# OpIoT_v_1_2.net
KiCad netlist of a schematic drawn in EAGLE
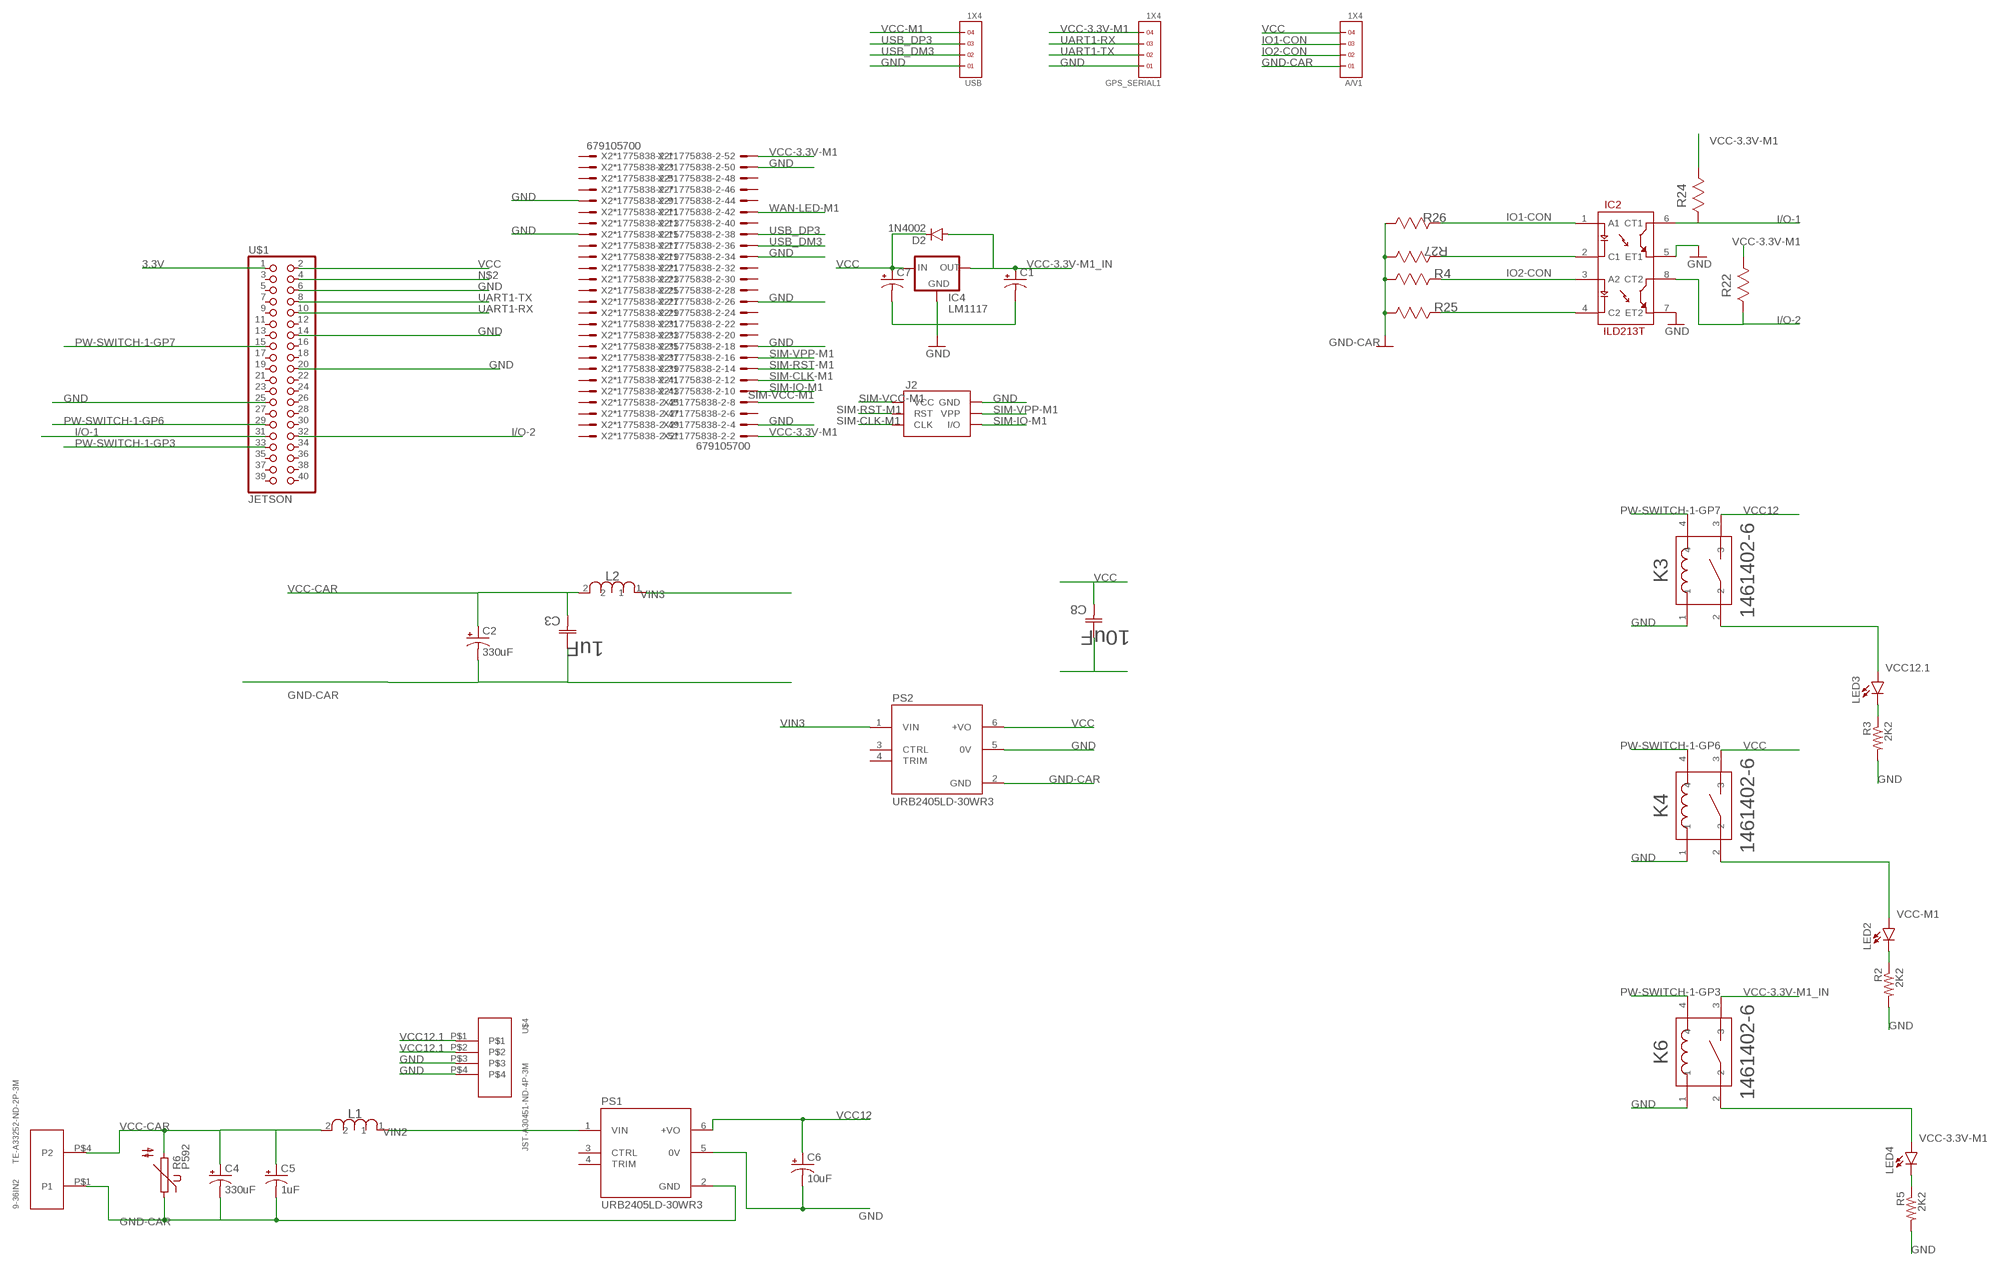
[diagram p0: schematic, sheet 1]

(export (version "E")
  (design (tool "Eeschema 10.0.6"))
  (components
    (comp (ref "9-36IN2")
      (value "TE-A33252-ND-2P-3M")
      (footprint "eagle-import:TE-A33252-ND-2P-3M")
      (libsource (lib "eagle-import") (part "TE-A33252-ND-2P-3M"))
    )
    (comp (ref "A/V1")
      (value "1X4")
      (footprint "eagle-import:1X4")
      (libsource (lib "eagle-import") (part "1X4"))
    )
    (comp (ref "C1")
      (value "CAP_POL1206-KIT")
      (footprint "eagle-import:EIA3216-KIT")
      (libsource (lib "eagle-import") (part "CAP_POL1206-KIT"))
    )
    (comp (ref "C2")
      (value "330uF")
      (footprint "eagle-import:UD-10X10_NICHICON")
      (libsource (lib "eagle-import") (part "CPOL-USUD-10X10"))
    )
    (comp (ref "C3")
      (value "1uF")
      (footprint "eagle-import:CAPC3216X110N")
      (fields (field (name "MPN") "C1206C105K5RACTU") (field (name "TOLERANCE") "±10%"))
      (libsource (lib "eagle-import") (part "C1206C105K5RACTU"))
    )
    (comp (ref "C4")
      (value "330uF")
      (footprint "eagle-import:UD-10X10_NICHICON")
      (libsource (lib "eagle-import") (part "CPOL-USUD-10X10"))
    )
    (comp (ref "C5")
      (value "1uF")
      (footprint "eagle-import:EIA3216-KIT")
      (libsource (lib "eagle-import") (part "CAP_POL1206-KIT"))
    )
    (comp (ref "C6")
      (value "10uF")
      (footprint "eagle-import:EIA3216-KIT")
      (libsource (lib "eagle-import") (part "CAP_POL1206-KIT"))
    )
    (comp (ref "C7")
      (value "CAP_POL1206-KIT")
      (footprint "eagle-import:EIA3216-KIT")
      (libsource (lib "eagle-import") (part "CAP_POL1206-KIT"))
    )
    (comp (ref "C8")
      (value "10uF")
      (footprint "eagle-import:CAPC3216X110N")
      (fields (field (name "MPN") "C1206C105K5RACTU") (field (name "TOLERANCE") "±10%"))
      (libsource (lib "eagle-import") (part "C1206C105K5RACTU"))
    )
    (comp (ref "D2")
      (value "1N4002")
      (footprint "eagle-import:SMA-DIODE-KIT")
      (libsource (lib "eagle-import") (part "DIODESMA-KIT"))
    )
    (comp (ref "GPS_SERIAL1")
      (value "1X4")
      (footprint "eagle-import:1X4")
      (libsource (lib "eagle-import") (part "1X4"))
    )
    (comp (ref "IC2")
      (value "ILD213T")
      (footprint "eagle-import:SO08")
      (libsource (lib "eagle-import") (part "ILD213T"))
    )
    (comp (ref "IC4")
      (value "LM1117")
      (footprint "eagle-import:SOT223")
      (fields (field (name "MF") "Texas Instruments") (field (name "MP") "LM1117MP-3.3/NOPB"))
      (libsource (lib "eagle-import") (part "LM1117"))
    )
    (comp (ref "J2")
      (value "SIMHOLDERSIM")
      (footprint "eagle-import:SIMHOLDER")
      (libsource (lib "eagle-import") (part "SIMHOLDERSIM"))
    )
    (comp (ref "K3")
      (value "1461402-6")
      (footprint "eagle-import:RELAY_1461402-6")
      (fields (field (name "MF") "TE Connectivity") (field (name "MP") "OJE-SH-112HM,000"))
      (libsource (lib "eagle-import") (part "1461402-6"))
    )
    (comp (ref "K4")
      (value "1461402-6")
      (footprint "eagle-import:RELAY_1461402-6")
      (fields (field (name "MF") "TE Connectivity") (field (name "MP") "OJE-SH-112HM,000"))
      (libsource (lib "eagle-import") (part "1461402-6"))
    )
    (comp (ref "K6")
      (value "1461402-6")
      (footprint "eagle-import:RELAY_1461402-6")
      (fields (field (name "MF") "TE Connectivity") (field (name "MP") "OJE-SH-112HM,000"))
      (libsource (lib "eagle-import") (part "1461402-6"))
    )
    (comp (ref "L1")
      (value "4.7uH")
      (footprint "eagle-import:INDC3225X22N")
      (fields (field (name "MPN") "PM1210-1R0J-RC") (field (name "TOLERANCE") "±5 %"))
      (libsource (lib "eagle-import") (part "PM1210-1R0J-RC"))
    )
    (comp (ref "L2")
      (value "4.7uH")
      (footprint "eagle-import:INDC3225X22N")
      (fields (field (name "MPN") "PM1210-1R0J-RC") (field (name "TOLERANCE") "±5 %"))
      (libsource (lib "eagle-import") (part "PM1210-1R0J-RC"))
    )
    (comp (ref "LED2")
      (value "LEDCHIPLED_1206")
      (footprint "eagle-import:CHIPLED_1206")
      (libsource (lib "eagle-import") (part "LEDCHIPLED_1206"))
    )
    (comp (ref "LED3")
      (value "LEDCHIPLED_1206")
      (footprint "eagle-import:CHIPLED_1206")
      (libsource (lib "eagle-import") (part "LEDCHIPLED_1206"))
    )
    (comp (ref "LED4")
      (value "LEDCHIPLED_1206")
      (footprint "eagle-import:CHIPLED_1206")
      (libsource (lib "eagle-import") (part "LEDCHIPLED_1206"))
    )
    (comp (ref "PS1")
      (value "URB2405LD-30WR3")
      (footprint "eagle-import:CONV_URB2405LD-30WR3")
      (fields (field (name "MF") "MORNSUN"))
      (libsource (lib "eagle-import") (part "URB2405LD-30WR3"))
    )
    (comp (ref "PS2")
      (value "URB2405LD-30WR3")
      (footprint "eagle-import:CONV_URB2405LD-30WR3")
      (fields (field (name "MF") "MORNSUN"))
      (libsource (lib "eagle-import") (part "URB2405LD-30WR3"))
    )
    (comp (ref "R2")
      (value "2K2")
      (footprint "eagle-import:M1206")
      (libsource (lib "eagle-import") (part "R-US_M1206"))
    )
    (comp (ref "R3")
      (value "2K2")
      (footprint "eagle-import:M1206")
      (libsource (lib "eagle-import") (part "R-US_M1206"))
    )
    (comp (ref "R4")
      (value "4K7")
      (footprint "eagle-import:RESC3216X71N")
      (fields (field (name "MPN") "ERJ-8ENF1501V") (field (name "TOLERANCE") "±1 %"))
      (libsource (lib "eagle-import") (part "ERJ-8ENF1501V"))
    )
    (comp (ref "R5")
      (value "2K2")
      (footprint "eagle-import:M1206")
      (libsource (lib "eagle-import") (part "R-US_M1206"))
    )
    (comp (ref "R6")
      (value "P592")
      (footprint "eagle-import:P592")
      (libsource (lib "eagle-import") (part "P592"))
    )
    (comp (ref "R22")
      (value "300K")
      (footprint "eagle-import:RESC3216X71N")
      (fields (field (name "MPN") "ERJ-8ENF1501V") (field (name "TOLERANCE") "±1 %"))
      (libsource (lib "eagle-import") (part "ERJ-8ENF1501V"))
    )
    (comp (ref "R24")
      (value "300K")
      (footprint "eagle-import:RESC3216X71N")
      (fields (field (name "MPN") "ERJ-8ENF1501V") (field (name "TOLERANCE") "±1 %"))
      (libsource (lib "eagle-import") (part "ERJ-8ENF1501V"))
    )
    (comp (ref "R25")
      (value "2.2K")
      (footprint "eagle-import:RESC3216X71N")
      (fields (field (name "MPN") "ERJ-8ENF1501V") (field (name "TOLERANCE") "±1 %"))
      (libsource (lib "eagle-import") (part "ERJ-8ENF1501V"))
    )
    (comp (ref "R26")
      (value "4K7")
      (footprint "eagle-import:RESC3216X71N")
      (fields (field (name "MPN") "ERJ-8ENF1501V") (field (name "TOLERANCE") "±1 %"))
      (libsource (lib "eagle-import") (part "ERJ-8ENF1501V"))
    )
    (comp (ref "R27")
      (value "2.2K")
      (footprint "eagle-import:RESC3216X71N")
      (fields (field (name "MPN") "ERJ-8ENF1501V") (field (name "TOLERANCE") "±1 %"))
      (libsource (lib "eagle-import") (part "ERJ-8ENF1501V"))
    )
    (comp (ref "U$1")
      (value "JETSON")
      (footprint "eagle-import:2X20")
      (libsource (lib "eagle-import") (part "JETSON"))
    )
    (comp (ref "U$4")
      (value "JST-A30451-ND-4P-3M")
      (footprint "eagle-import:TE-A30451-4P-TH-3M")
      (libsource (lib "eagle-import") (part "JST-A30451-ND-4P-3M"))
    )
    (comp (ref "USB")
      (value "1X4")
      (footprint "eagle-import:1X4")
      (libsource (lib "eagle-import") (part "1X4"))
    )
    (comp (ref "X2*1775838-2")
      (value "679105700")
      (footprint "eagle-import:679105700")
      (fields (field (name "MF") "MOLEX") (field (name "MPN") "67910-5700"))
      (libsource (lib "eagle-import") (part "679105700"))
    )
  )
  (nets
    (net (code "1") (name "/3.3V") (class "Default")
      (node (ref "U$1") (pin "1") (pinfunction "1_1") (pintype "passive"))
    )
    (net (code "2") (name "/IO1-CON") (class "Default")
      (node (ref "A/V1") (pin "3") (pinfunction "3_3") (pintype "bidirectional"))
      (node (ref "IC2") (pin "1") (pinfunction "A1_1") (pintype "bidirectional"))
      (node (ref "R26") (pin "1") (pinfunction "R1_1") (pintype "passive"))
    )
    (net (code "3") (name "/IO2-CON") (class "Default")
      (node (ref "A/V1") (pin "2") (pinfunction "2_2") (pintype "bidirectional"))
      (node (ref "IC2") (pin "3") (pinfunction "A2_3") (pintype "bidirectional"))
      (node (ref "R4") (pin "1") (pinfunction "R1_1") (pintype "passive"))
    )
    (net (code "4") (name "/I{slash}O-1") (class "Default")
      (node (ref "IC2") (pin "6") (pinfunction "CT1_6") (pintype "bidirectional"))
      (node (ref "R24") (pin "2") (pinfunction "R2_2") (pintype "passive"))
      (node (ref "U$1") (pin "31") (pinfunction "31_31") (pintype "passive"))
    )
    (net (code "5") (name "/I{slash}O-2") (class "Default")
      (node (ref "IC2") (pin "8") (pinfunction "CT2_8") (pintype "bidirectional"))
      (node (ref "R22") (pin "2") (pinfunction "R2_2") (pintype "passive"))
      (node (ref "U$1") (pin "32") (pinfunction "32_32") (pintype "passive"))
    )
    (net (code "6") (name "/N$2") (class "Default")
      (node (ref "U$1") (pin "4") (pinfunction "4_4") (pintype "passive"))
    )
    (net (code "7") (name "/PW-SWITCH-1-GP3") (class "Default")
      (node (ref "K6") (pin "4") (pinfunction "4_4") (pintype "passive"))
      (node (ref "U$1") (pin "33") (pinfunction "33_33") (pintype "passive"))
    )
    (net (code "8") (name "/PW-SWITCH-1-GP6") (class "Default")
      (node (ref "K4") (pin "4") (pinfunction "4_4") (pintype "passive"))
      (node (ref "U$1") (pin "29") (pinfunction "29_29") (pintype "passive"))
    )
    (net (code "9") (name "/PW-SWITCH-1-GP7") (class "Default")
      (node (ref "K3") (pin "4") (pinfunction "4_4") (pintype "passive"))
      (node (ref "U$1") (pin "15") (pinfunction "15_15") (pintype "passive"))
    )
    (net (code "10") (name "/SIM-CLK-M1") (class "Default")
      (node (ref "J2") (pin "C3") (pinfunction "CLK_C3") (pintype "input"))
      (node (ref "X2*1775838-2") (pin "12") (pinfunction "S_12") (pintype "passive"))
    )
    (net (code "11") (name "/SIM-IO-M1") (class "Default")
      (node (ref "J2") (pin "C7") (pinfunction "I/O_C7") (pintype "bidirectional"))
      (node (ref "X2*1775838-2") (pin "10") (pinfunction "S_10") (pintype "passive"))
    )
    (net (code "12") (name "/SIM-RST-M1") (class "Default")
      (node (ref "J2") (pin "C2") (pinfunction "RST_C2") (pintype "input"))
      (node (ref "X2*1775838-2") (pin "14") (pinfunction "S_14") (pintype "passive"))
    )
    (net (code "13") (name "/SIM-VCC-M1") (class "Default")
      (node (ref "J2") (pin "C1") (pinfunction "VCC_C1") (pintype "power_in"))
      (node (ref "X2*1775838-2") (pin "8") (pinfunction "S_8") (pintype "passive"))
    )
    (net (code "14") (name "/SIM-VPP-M1") (class "Default")
      (node (ref "J2") (pin "C6") (pinfunction "VPP_C6") (pintype "input"))
      (node (ref "X2*1775838-2") (pin "16") (pinfunction "S_16") (pintype "passive"))
    )
    (net (code "15") (name "/UART1-RX") (class "Default")
      (node (ref "GPS_SERIAL1") (pin "3") (pinfunction "3_3") (pintype "bidirectional"))
      (node (ref "U$1") (pin "10") (pinfunction "10_10") (pintype "passive"))
    )
    (net (code "16") (name "/UART1-TX") (class "Default")
      (node (ref "GPS_SERIAL1") (pin "2") (pinfunction "2_2") (pintype "bidirectional"))
      (node (ref "U$1") (pin "8") (pinfunction "8_8") (pintype "passive"))
    )
    (net (code "17") (name "/USB_DM3") (class "Default")
      (node (ref "USB") (pin "2") (pinfunction "2_2") (pintype "bidirectional"))
      (node (ref "X2*1775838-2") (pin "36") (pinfunction "S_36") (pintype "passive"))
    )
    (net (code "18") (name "/USB_DP3") (class "Default")
      (node (ref "USB") (pin "3") (pinfunction "3_3") (pintype "bidirectional"))
      (node (ref "X2*1775838-2") (pin "38") (pinfunction "S_38") (pintype "passive"))
    )
    (net (code "19") (name "/VCC") (class "Default")
      (node (ref "A/V1") (pin "4") (pinfunction "4_4") (pintype "bidirectional"))
      (node (ref "C7") (pin "A") (pinfunction "+_A") (pintype "passive"))
      (node (ref "C8") (pin "2") (pinfunction "C2_2") (pintype "passive"))
      (node (ref "D2") (pin "C") (pinfunction "C_C") (pintype "passive"))
      (node (ref "IC4") (pin "3") (pinfunction "IN_3") (pintype "input"))
      (node (ref "K4") (pin "3") (pinfunction "3_3") (pintype "passive"))
      (node (ref "PS2") (pin "6") (pinfunction "+VO_6") (pintype "output"))
      (node (ref "U$1") (pin "2") (pinfunction "2_2") (pintype "passive"))
    )
    (net (code "20") (name "/VCC-3.3V-M1") (class "Default")
      (node (ref "GPS_SERIAL1") (pin "4") (pinfunction "4_4") (pintype "bidirectional"))
      (node (ref "K6") (pin "2") (pinfunction "2_2") (pintype "passive"))
      (node (ref "LED4") (pin "A") (pinfunction "A_A") (pintype "passive"))
      (node (ref "R22") (pin "1") (pinfunction "R1_1") (pintype "passive"))
      (node (ref "R24") (pin "1") (pinfunction "R1_1") (pintype "passive"))
      (node (ref "X2*1775838-2") (pin "2") (pinfunction "S_2") (pintype "passive"))
      (node (ref "X2*1775838-2") (pin "52") (pinfunction "S_52") (pintype "passive"))
    )
    (net (code "21") (name "/VCC-3.3V-M1_IN") (class "Default")
      (node (ref "C1") (pin "A") (pinfunction "+_A") (pintype "passive"))
      (node (ref "D2") (pin "A") (pinfunction "A_A") (pintype "passive"))
      (node (ref "IC4") (pin "2") (pinfunction "OUT_2") (pintype "passive"))
      (node (ref "K6") (pin "3") (pinfunction "3_3") (pintype "passive"))
    )
    (net (code "22") (name "/VCC-CAR") (class "Default")
      (node (ref "9-36IN2") (pin "P$4") (pinfunction "P2_P$4") (pintype "bidirectional"))
      (node (ref "C2") (pin "+") (pinfunction "+_+") (pintype "passive"))
      (node (ref "C3") (pin "2") (pinfunction "C2_2") (pintype "passive"))
      (node (ref "C4") (pin "+") (pinfunction "+_+") (pintype "passive"))
      (node (ref "C5") (pin "A") (pinfunction "+_A") (pintype "passive"))
      (node (ref "L1") (pin "2") (pinfunction "2_2") (pintype "passive"))
      (node (ref "L2") (pin "2") (pinfunction "2_2") (pintype "passive"))
      (node (ref "R6") (pin "2") (pinfunction "2_2") (pintype "passive"))
    )
    (net (code "23") (name "/VCC-M1") (class "Default")
      (node (ref "K4") (pin "2") (pinfunction "2_2") (pintype "passive"))
      (node (ref "LED2") (pin "A") (pinfunction "A_A") (pintype "passive"))
      (node (ref "USB") (pin "4") (pinfunction "4_4") (pintype "bidirectional"))
    )
    (net (code "24") (name "/VCC12") (class "Default")
      (node (ref "C6") (pin "A") (pinfunction "+_A") (pintype "passive"))
      (node (ref "K3") (pin "3") (pinfunction "3_3") (pintype "passive"))
      (node (ref "PS1") (pin "6") (pinfunction "+VO_6") (pintype "output"))
    )
    (net (code "25") (name "/VCC12.1") (class "Default")
      (node (ref "K3") (pin "2") (pinfunction "2_2") (pintype "passive"))
      (node (ref "LED3") (pin "A") (pinfunction "A_A") (pintype "passive"))
      (node (ref "U$4") (pin "P$1") (pinfunction "P$1_P$1") (pintype "bidirectional"))
      (node (ref "U$4") (pin "P$2") (pinfunction "P$2_P$2") (pintype "bidirectional"))
    )
    (net (code "26") (name "/VIN2") (class "Default")
      (node (ref "L1") (pin "1") (pinfunction "1_1") (pintype "passive"))
      (node (ref "PS1") (pin "1") (pinfunction "VIN_1") (pintype "input"))
    )
    (net (code "27") (name "/VIN3") (class "Default")
      (node (ref "L2") (pin "1") (pinfunction "1_1") (pintype "passive"))
      (node (ref "PS2") (pin "1") (pinfunction "VIN_1") (pintype "input"))
    )
    (net (code "28") (name "/WAN-LED-M1") (class "Default")
      (node (ref "X2*1775838-2") (pin "42") (pinfunction "S_42") (pintype "passive"))
    )
    (net (code "29") (name "GND") (class "Default")
      (node (ref "C1") (pin "C") (pinfunction "-_C") (pintype "passive"))
      (node (ref "C6") (pin "C") (pinfunction "-_C") (pintype "passive"))
      (node (ref "C7") (pin "C") (pinfunction "-_C") (pintype "passive"))
      (node (ref "C8") (pin "1") (pinfunction "C1_1") (pintype "passive"))
      (node (ref "GPS_SERIAL1") (pin "1") (pinfunction "1_1") (pintype "bidirectional"))
      (node (ref "IC2") (pin "5") (pinfunction "ET1_5") (pintype "bidirectional"))
      (node (ref "IC2") (pin "7") (pinfunction "ET2_7") (pintype "bidirectional"))
      (node (ref "IC4") (pin "1") (pinfunction "GND_1") (pintype "input"))
      (node (ref "J2") (pin "C5") (pinfunction "GND_C5") (pintype "power_in"))
      (node (ref "K3") (pin "1") (pinfunction "1_1") (pintype "passive"))
      (node (ref "K4") (pin "1") (pinfunction "1_1") (pintype "passive"))
      (node (ref "K6") (pin "1") (pinfunction "1_1") (pintype "passive"))
      (node (ref "PS1") (pin "5") (pinfunction "0V_5") (pintype "output"))
      (node (ref "PS2") (pin "5") (pinfunction "0V_5") (pintype "output"))
      (node (ref "R2") (pin "2") (pinfunction "2_2") (pintype "passive"))
      (node (ref "R3") (pin "2") (pinfunction "2_2") (pintype "passive"))
      (node (ref "R5") (pin "2") (pinfunction "2_2") (pintype "passive"))
      (node (ref "U$1") (pin "14") (pinfunction "14_14") (pintype "passive"))
      (node (ref "U$1") (pin "20") (pinfunction "20_20") (pintype "passive"))
      (node (ref "U$1") (pin "25") (pinfunction "25_25") (pintype "passive"))
      (node (ref "U$1") (pin "6") (pinfunction "6_6") (pintype "passive"))
      (node (ref "U$4") (pin "P$3") (pinfunction "P$3_P$3") (pintype "bidirectional"))
      (node (ref "U$4") (pin "P$4") (pinfunction "P$4_P$4") (pintype "bidirectional"))
      (node (ref "USB") (pin "1") (pinfunction "1_1") (pintype "bidirectional"))
      (node (ref "X2*1775838-2") (pin "15") (pinfunction "S_15") (pintype "passive"))
      (node (ref "X2*1775838-2") (pin "18") (pinfunction "S_18") (pintype "passive"))
      (node (ref "X2*1775838-2") (pin "26") (pinfunction "S_26") (pintype "passive"))
      (node (ref "X2*1775838-2") (pin "34") (pinfunction "S_34") (pintype "passive"))
      (node (ref "X2*1775838-2") (pin "4") (pinfunction "S_4") (pintype "passive"))
      (node (ref "X2*1775838-2") (pin "50") (pinfunction "S_50") (pintype "passive"))
      (node (ref "X2*1775838-2") (pin "9") (pinfunction "S_9") (pintype "passive"))
    )
    (net (code "30") (name "GND-CAR") (class "Default")
      (node (ref "9-36IN2") (pin "P$1") (pinfunction "P1_P$1") (pintype "bidirectional"))
      (node (ref "A/V1") (pin "1") (pinfunction "1_1") (pintype "bidirectional"))
      (node (ref "C2") (pin "-") (pinfunction "-_-") (pintype "passive"))
      (node (ref "C3") (pin "1") (pinfunction "C1_1") (pintype "passive"))
      (node (ref "C4") (pin "-") (pinfunction "-_-") (pintype "passive"))
      (node (ref "C5") (pin "C") (pinfunction "-_C") (pintype "passive"))
      (node (ref "PS1") (pin "2") (pinfunction "GND_2") (pintype "power_in"))
      (node (ref "PS2") (pin "2") (pinfunction "GND_2") (pintype "power_in"))
      (node (ref "R25") (pin "1") (pinfunction "R1_1") (pintype "passive"))
      (node (ref "R26") (pin "2") (pinfunction "R2_2") (pintype "passive"))
      (node (ref "R27") (pin "1") (pinfunction "R1_1") (pintype "passive"))
      (node (ref "R4") (pin "2") (pinfunction "R2_2") (pintype "passive"))
      (node (ref "R6") (pin "1") (pinfunction "1_1") (pintype "passive"))
    )
    (net (code "31") (name "Net-(IC2-C1)") (class "Default")
      (node (ref "IC2") (pin "2") (pinfunction "C1_2") (pintype "bidirectional"))
      (node (ref "R27") (pin "2") (pinfunction "R2_2") (pintype "passive"))
    )
    (net (code "32") (name "Net-(IC2-C2)") (class "Default")
      (node (ref "IC2") (pin "4") (pinfunction "C2_4") (pintype "bidirectional"))
      (node (ref "R25") (pin "2") (pinfunction "R2_2") (pintype "passive"))
    )
    (net (code "33") (name "Net-(LED2-PadC)") (class "Default")
      (node (ref "LED2") (pin "C") (pinfunction "C_C") (pintype "passive"))
      (node (ref "R2") (pin "1") (pinfunction "1_1") (pintype "passive"))
    )
    (net (code "34") (name "Net-(LED3-PadC)") (class "Default")
      (node (ref "LED3") (pin "C") (pinfunction "C_C") (pintype "passive"))
      (node (ref "R3") (pin "1") (pinfunction "1_1") (pintype "passive"))
    )
    (net (code "35") (name "Net-(LED4-PadC)") (class "Default")
      (node (ref "LED4") (pin "C") (pinfunction "C_C") (pintype "passive"))
      (node (ref "R5") (pin "1") (pinfunction "1_1") (pintype "passive"))
    )
    (net (code "36") (name "unconnected-(PS1-CTRL-Pad3)") (class "Default")
      (node (ref "PS1") (pin "3") (pinfunction "CTRL_3") (pintype "input"))
    )
    (net (code "37") (name "unconnected-(PS1-TRIM-Pad4)") (class "Default")
      (node (ref "PS1") (pin "4") (pinfunction "TRIM_4") (pintype "input"))
    )
    (net (code "38") (name "unconnected-(PS2-CTRL-Pad3)") (class "Default")
      (node (ref "PS2") (pin "3") (pinfunction "CTRL_3") (pintype "input"))
    )
    (net (code "39") (name "unconnected-(PS2-TRIM-Pad4)") (class "Default")
      (node (ref "PS2") (pin "4") (pinfunction "TRIM_4") (pintype "input"))
    )
    (net (code "40") (name "unconnected-(U$1-Pad3)") (class "Default")
      (node (ref "U$1") (pin "3") (pinfunction "3_3") (pintype "passive"))
    )
    (net (code "41") (name "unconnected-(U$1-Pad5)") (class "Default")
      (node (ref "U$1") (pin "5") (pinfunction "5_5") (pintype "passive"))
    )
    (net (code "42") (name "unconnected-(U$1-Pad7)") (class "Default")
      (node (ref "U$1") (pin "7") (pinfunction "7_7") (pintype "passive"))
    )
    (net (code "43") (name "unconnected-(U$1-Pad9)") (class "Default")
      (node (ref "U$1") (pin "9") (pinfunction "9_9") (pintype "passive"))
    )
    (net (code "44") (name "unconnected-(U$1-Pad11)") (class "Default")
      (node (ref "U$1") (pin "11") (pinfunction "11_11") (pintype "passive"))
    )
    (net (code "45") (name "unconnected-(U$1-Pad12)") (class "Default")
      (node (ref "U$1") (pin "12") (pinfunction "12_12") (pintype "passive"))
    )
    (net (code "46") (name "unconnected-(U$1-Pad13)") (class "Default")
      (node (ref "U$1") (pin "13") (pinfunction "13_13") (pintype "passive"))
    )
    (net (code "47") (name "unconnected-(U$1-Pad16)") (class "Default")
      (node (ref "U$1") (pin "16") (pinfunction "16_16") (pintype "passive"))
    )
    (net (code "48") (name "unconnected-(U$1-Pad17)") (class "Default")
      (node (ref "U$1") (pin "17") (pinfunction "17_17") (pintype "passive"))
    )
    (net (code "49") (name "unconnected-(U$1-Pad18)") (class "Default")
      (node (ref "U$1") (pin "18") (pinfunction "18_18") (pintype "passive"))
    )
    (net (code "50") (name "unconnected-(U$1-Pad19)") (class "Default")
      (node (ref "U$1") (pin "19") (pinfunction "19_19") (pintype "passive"))
    )
    (net (code "51") (name "unconnected-(U$1-Pad21)") (class "Default")
      (node (ref "U$1") (pin "21") (pinfunction "21_21") (pintype "passive"))
    )
    (net (code "52") (name "unconnected-(U$1-Pad22)") (class "Default")
      (node (ref "U$1") (pin "22") (pinfunction "22_22") (pintype "passive"))
    )
    (net (code "53") (name "unconnected-(U$1-Pad23)") (class "Default")
      (node (ref "U$1") (pin "23") (pinfunction "23_23") (pintype "passive"))
    )
    (net (code "54") (name "unconnected-(U$1-Pad24)") (class "Default")
      (node (ref "U$1") (pin "24") (pinfunction "24_24") (pintype "passive"))
    )
    (net (code "55") (name "unconnected-(U$1-Pad26)") (class "Default")
      (node (ref "U$1") (pin "26") (pinfunction "26_26") (pintype "passive"))
    )
    (net (code "56") (name "unconnected-(U$1-Pad27)") (class "Default")
      (node (ref "U$1") (pin "27") (pinfunction "27_27") (pintype "passive"))
    )
    (net (code "57") (name "unconnected-(U$1-Pad28)") (class "Default")
      (node (ref "U$1") (pin "28") (pinfunction "28_28") (pintype "passive"))
    )
    (net (code "58") (name "unconnected-(U$1-Pad30)") (class "Default")
      (node (ref "U$1") (pin "30") (pinfunction "30_30") (pintype "passive"))
    )
    (net (code "59") (name "unconnected-(U$1-Pad34)") (class "Default")
      (node (ref "U$1") (pin "34") (pinfunction "34_34") (pintype "passive"))
    )
    (net (code "60") (name "unconnected-(U$1-Pad35)") (class "Default")
      (node (ref "U$1") (pin "35") (pinfunction "35_35") (pintype "passive"))
    )
    (net (code "61") (name "unconnected-(U$1-Pad36)") (class "Default")
      (node (ref "U$1") (pin "36") (pinfunction "36_36") (pintype "passive"))
    )
    (net (code "62") (name "unconnected-(U$1-Pad37)") (class "Default")
      (node (ref "U$1") (pin "37") (pinfunction "37_37") (pintype "passive"))
    )
    (net (code "63") (name "unconnected-(U$1-Pad38)") (class "Default")
      (node (ref "U$1") (pin "38") (pinfunction "38_38") (pintype "passive"))
    )
    (net (code "64") (name "unconnected-(U$1-Pad39)") (class "Default")
      (node (ref "U$1") (pin "39") (pinfunction "39_39") (pintype "passive"))
    )
    (net (code "65") (name "unconnected-(U$1-Pad40)") (class "Default")
      (node (ref "U$1") (pin "40") (pinfunction "40_40") (pintype "passive"))
    )
    (net (code "66") (name "unconnected-(X2*1775838-2A-S-Pad1)") (class "Default")
      (node (ref "X2*1775838-2") (pin "1") (pinfunction "S_1") (pintype "passive"))
    )
    (net (code "67") (name "unconnected-(X2*1775838-2AA-S-Pad33)") (class "Default")
      (node (ref "X2*1775838-2") (pin "33") (pinfunction "S_33") (pintype "passive"))
    )
    (net (code "68") (name "unconnected-(X2*1775838-2AC-S-Pad35)") (class "Default")
      (node (ref "X2*1775838-2") (pin "35") (pinfunction "S_35") (pintype "passive"))
    )
    (net (code "69") (name "unconnected-(X2*1775838-2AE-S-Pad37)") (class "Default")
      (node (ref "X2*1775838-2") (pin "37") (pinfunction "S_37") (pintype "passive"))
    )
    (net (code "70") (name "unconnected-(X2*1775838-2AG-S-Pad39)") (class "Default")
      (node (ref "X2*1775838-2") (pin "39") (pinfunction "S_39") (pintype "passive"))
    )
    (net (code "71") (name "unconnected-(X2*1775838-2AI-S-Pad40)") (class "Default")
      (node (ref "X2*1775838-2") (pin "40") (pinfunction "S_40") (pintype "passive"))
    )
    (net (code "72") (name "unconnected-(X2*1775838-2AJ-S-Pad41)") (class "Default")
      (node (ref "X2*1775838-2") (pin "41") (pinfunction "S_41") (pintype "passive"))
    )
    (net (code "73") (name "unconnected-(X2*1775838-2AL-S-Pad43)") (class "Default")
      (node (ref "X2*1775838-2") (pin "43") (pinfunction "S_43") (pintype "passive"))
    )
    (net (code "74") (name "unconnected-(X2*1775838-2AM-S-Pad44)") (class "Default")
      (node (ref "X2*1775838-2") (pin "44") (pinfunction "S_44") (pintype "passive"))
    )
    (net (code "75") (name "unconnected-(X2*1775838-2AN-S-Pad45)") (class "Default")
      (node (ref "X2*1775838-2") (pin "45") (pinfunction "S_45") (pintype "passive"))
    )
    (net (code "76") (name "unconnected-(X2*1775838-2AO-S-Pad46)") (class "Default")
      (node (ref "X2*1775838-2") (pin "46") (pinfunction "S_46") (pintype "passive"))
    )
    (net (code "77") (name "unconnected-(X2*1775838-2AP-S-Pad47)") (class "Default")
      (node (ref "X2*1775838-2") (pin "47") (pinfunction "S_47") (pintype "passive"))
    )
    (net (code "78") (name "unconnected-(X2*1775838-2AQ-S-Pad48)") (class "Default")
      (node (ref "X2*1775838-2") (pin "48") (pinfunction "S_48") (pintype "passive"))
    )
    (net (code "79") (name "unconnected-(X2*1775838-2AR-S-Pad49)") (class "Default")
      (node (ref "X2*1775838-2") (pin "49") (pinfunction "S_49") (pintype "passive"))
    )
    (net (code "80") (name "unconnected-(X2*1775838-2AS-S-Pad5)") (class "Default")
      (node (ref "X2*1775838-2") (pin "5") (pinfunction "S_5") (pintype "passive"))
    )
    (net (code "81") (name "unconnected-(X2*1775838-2AU-S-Pad51)") (class "Default")
      (node (ref "X2*1775838-2") (pin "51") (pinfunction "S_51") (pintype "passive"))
    )
    (net (code "82") (name "unconnected-(X2*1775838-2AW-S-Pad6)") (class "Default")
      (node (ref "X2*1775838-2") (pin "6") (pinfunction "S_6") (pintype "passive"))
    )
    (net (code "83") (name "unconnected-(X2*1775838-2AX-S-Pad7)") (class "Default")
      (node (ref "X2*1775838-2") (pin "7") (pinfunction "S_7") (pintype "passive"))
    )
    (net (code "84") (name "unconnected-(X2*1775838-2C-S-Pad11)") (class "Default")
      (node (ref "X2*1775838-2") (pin "11") (pinfunction "S_11") (pintype "passive"))
    )
    (net (code "85") (name "unconnected-(X2*1775838-2E-S-Pad13)") (class "Default")
      (node (ref "X2*1775838-2") (pin "13") (pinfunction "S_13") (pintype "passive"))
    )
    (net (code "86") (name "unconnected-(X2*1775838-2I-S-Pad17)") (class "Default")
      (node (ref "X2*1775838-2") (pin "17") (pinfunction "S_17") (pintype "passive"))
    )
    (net (code "87") (name "unconnected-(X2*1775838-2K-S-Pad19)") (class "Default")
      (node (ref "X2*1775838-2") (pin "19") (pinfunction "S_19") (pintype "passive"))
    )
    (net (code "88") (name "unconnected-(X2*1775838-2M-S-Pad20)") (class "Default")
      (node (ref "X2*1775838-2") (pin "20") (pinfunction "S_20") (pintype "passive"))
    )
    (net (code "89") (name "unconnected-(X2*1775838-2N-S-Pad21)") (class "Default")
      (node (ref "X2*1775838-2") (pin "21") (pinfunction "S_21") (pintype "passive"))
    )
    (net (code "90") (name "unconnected-(X2*1775838-2O-S-Pad22)") (class "Default")
      (node (ref "X2*1775838-2") (pin "22") (pinfunction "S_22") (pintype "passive"))
    )
    (net (code "91") (name "unconnected-(X2*1775838-2P-S-Pad23)") (class "Default")
      (node (ref "X2*1775838-2") (pin "23") (pinfunction "S_23") (pintype "passive"))
    )
    (net (code "92") (name "unconnected-(X2*1775838-2Q-S-Pad24)") (class "Default")
      (node (ref "X2*1775838-2") (pin "24") (pinfunction "S_24") (pintype "passive"))
    )
    (net (code "93") (name "unconnected-(X2*1775838-2R-S-Pad25)") (class "Default")
      (node (ref "X2*1775838-2") (pin "25") (pinfunction "S_25") (pintype "passive"))
    )
    (net (code "94") (name "unconnected-(X2*1775838-2T-S-Pad27)") (class "Default")
      (node (ref "X2*1775838-2") (pin "27") (pinfunction "S_27") (pintype "passive"))
    )
    (net (code "95") (name "unconnected-(X2*1775838-2U-S-Pad28)") (class "Default")
      (node (ref "X2*1775838-2") (pin "28") (pinfunction "S_28") (pintype "passive"))
    )
    (net (code "96") (name "unconnected-(X2*1775838-2V-S-Pad29)") (class "Default")
      (node (ref "X2*1775838-2") (pin "29") (pinfunction "S_29") (pintype "passive"))
    )
    (net (code "97") (name "unconnected-(X2*1775838-2W-S-Pad3)") (class "Default")
      (node (ref "X2*1775838-2") (pin "3") (pinfunction "S_3") (pintype "passive"))
    )
    (net (code "98") (name "unconnected-(X2*1775838-2X-S-Pad30)") (class "Default")
      (node (ref "X2*1775838-2") (pin "30") (pinfunction "S_30") (pintype "passive"))
    )
    (net (code "99") (name "unconnected-(X2*1775838-2Y-S-Pad31)") (class "Default")
      (node (ref "X2*1775838-2") (pin "31") (pinfunction "S_31") (pintype "passive"))
    )
    (net (code "100") (name "unconnected-(X2*1775838-2Z-S-Pad32)") (class "Default")
      (node (ref "X2*1775838-2") (pin "32") (pinfunction "S_32") (pintype "passive"))
    )
  )
)
